# design.net
KiCad netlist of a schematic drawn in Altium Designer
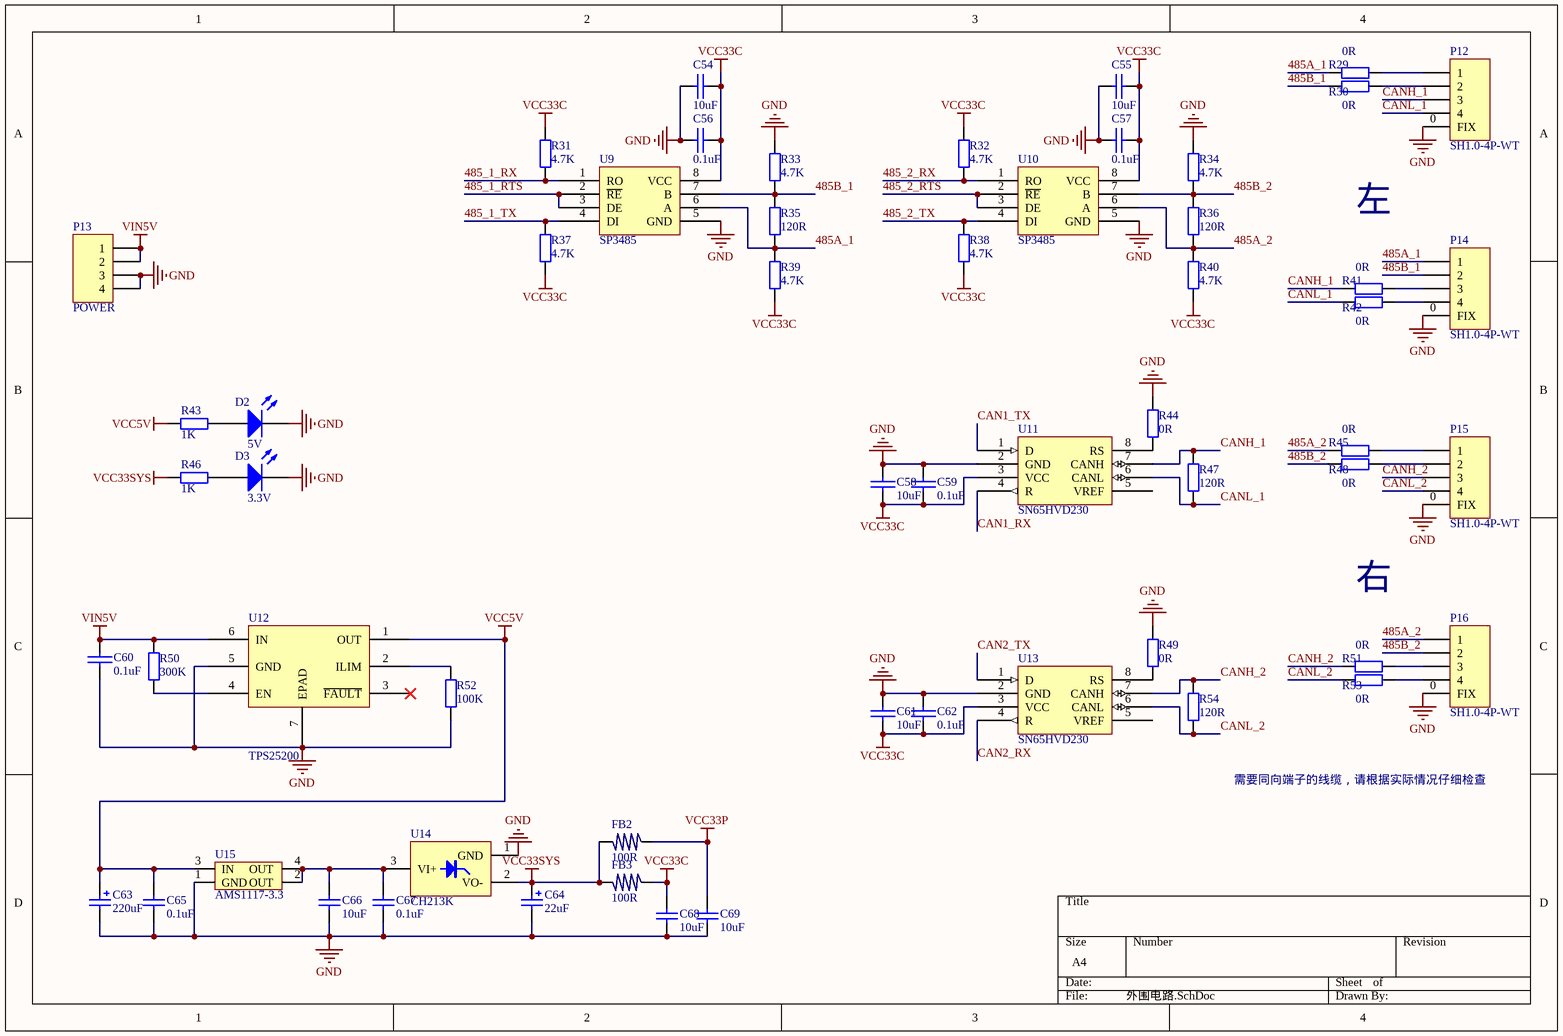
[diagram p0: 外围电路.SchDoc]

(export (version "E")
  (design (tool "Eeschema 10.0.6"))
  (components
    (comp (ref "C54")
      (value "10uF")
      (footprint "C0805_M")
      (description "Capacitor")
      (libsource (lib "*") (part "CAP"))
    )
    (comp (ref "C55")
      (value "10uF")
      (footprint "C0805_M")
      (description "Capacitor")
      (libsource (lib "*") (part "CAP"))
    )
    (comp (ref "C56")
      (value "0.1uF")
      (footprint "C0805_M")
      (description "Capacitor")
      (libsource (lib "*") (part "CAP"))
    )
    (comp (ref "C57")
      (value "0.1uF")
      (footprint "C0805_M")
      (description "Capacitor")
      (libsource (lib "*") (part "CAP"))
    )
    (comp (ref "C58")
      (value "10uF")
      (footprint "C0805_M")
      (description "Capacitor")
      (libsource (lib "*") (part "CAP"))
    )
    (comp (ref "C59")
      (value "0.1uF")
      (footprint "C0805_M")
      (description "Capacitor")
      (libsource (lib "*") (part "CAP"))
    )
    (comp (ref "C60")
      (value "0.1uF")
      (footprint "C0805_M")
      (description "Capacitor")
      (libsource (lib "*") (part "CAP"))
    )
    (comp (ref "C61")
      (value "10uF")
      (footprint "C0805_M")
      (description "Capacitor")
      (libsource (lib "*") (part "CAP"))
    )
    (comp (ref "C62")
      (value "0.1uF")
      (footprint "C0805_M")
      (description "Capacitor")
      (libsource (lib "*") (part "CAP"))
    )
    (comp (ref "C63")
      (value "220uF")
      (footprint "CS 6*6 - R")
      (description "Polarized Capacitor (Axial)")
      (fields (field (name "PUBLISHER") "Altium Limited"))
      (libsource (lib "Miscellaneous Devices") (part "Cap Pol2"))
    )
    (comp (ref "C64")
      (value "22uF")
      (footprint "CS 6*6 - R")
      (description "Polarized Capacitor (Axial)")
      (fields (field (name "PUBLISHER") "Altium Limited"))
      (libsource (lib "Miscellaneous Devices") (part "Cap Pol2"))
    )
    (comp (ref "C65")
      (value "0.1uF")
      (footprint "C0805_M")
      (description "Capacitor")
      (fields (field (name "PUBLISHER") "Altium Limited"))
      (libsource (lib "Miscellaneous Devices") (part "Cap"))
    )
    (comp (ref "C66")
      (value "10uF")
      (footprint "C0805_M")
      (description "Capacitor")
      (fields (field (name "PUBLISHER") "Altium Limited"))
      (libsource (lib "Miscellaneous Devices") (part "Cap"))
    )
    (comp (ref "C67")
      (value "0.1uF")
      (footprint "C0805_M")
      (description "Capacitor")
      (fields (field (name "PUBLISHER") "Altium Limited"))
      (libsource (lib "Miscellaneous Devices") (part "Cap"))
    )
    (comp (ref "C68")
      (value "10uF")
      (footprint "C0805_M")
      (description "Capacitor")
      (fields (field (name "PUBLISHER") "Altium Limited"))
      (libsource (lib "Miscellaneous Devices") (part "Cap"))
    )
    (comp (ref "C69")
      (value "10uF")
      (footprint "C0805_M")
      (description "Capacitor")
      (fields (field (name "PUBLISHER") "Altium Limited"))
      (libsource (lib "Miscellaneous Devices") (part "Cap"))
    )
    (comp (ref "D2")
      (value "5V")
      (footprint "LED0805_G")
      (description "Typical RED GaAs LED")
      (fields (field (name "PUBLISHER") "Altium Limited"))
      (libsource (lib "Miscellaneous Devices") (part "LED1"))
    )
    (comp (ref "D3")
      (value "3.3V")
      (footprint "LED0805_G")
      (description "Typical RED GaAs LED")
      (fields (field (name "PUBLISHER") "Altium Limited"))
      (libsource (lib "Miscellaneous Devices") (part "LED1"))
    )
    (comp (ref "FB2") (value "100R") (footprint "R0805_M") (libsource (lib "EXPLORER") (part "L")))
    (comp (ref "FB3") (value "100R") (footprint "R0805_M") (libsource (lib "EXPLORER") (part "L")))
    (comp (ref "P12")
      (value "SH1.0-4P-WT")
      (footprint "SH1.0-LT-4P")
      (description "Header, 5-Pin")
      (fields (field (name "PUBLISHER") "Altium Limited"))
      (libsource (lib "Miscellaneous Connectors") (part "Header 5"))
    )
    (comp (ref "P13")
      (value "POWER")
      (footprint "XH2.54-LI-4P")
      (description "Header, 4-Pin")
      (fields (field (name "PUBLISHER") "Altium Limited"))
      (libsource (lib "Miscellaneous Connectors") (part "Header 4"))
    )
    (comp (ref "P14")
      (value "SH1.0-4P-WT")
      (footprint "SH1.0-LT-4P")
      (description "Header, 5-Pin")
      (fields (field (name "PUBLISHER") "Altium Limited"))
      (libsource (lib "Miscellaneous Connectors") (part "Header 5"))
    )
    (comp (ref "P15")
      (value "SH1.0-4P-WT")
      (footprint "SH1.0-LT-4P")
      (description "Header, 5-Pin")
      (fields (field (name "PUBLISHER") "Altium Limited"))
      (libsource (lib "Miscellaneous Connectors") (part "Header 5"))
    )
    (comp (ref "P16")
      (value "SH1.0-4P-WT")
      (footprint "SH1.0-LT-4P")
      (description "Header, 5-Pin")
      (fields (field (name "PUBLISHER") "Altium Limited"))
      (libsource (lib "Miscellaneous Connectors") (part "Header 5"))
    )
    (comp (ref "R29")
      (value "0R")
      (footprint "R0805_M")
      (description "Resistor")
      (fields (field (name "PUBLISHER") "Altium Limited"))
      (libsource (lib "Miscellaneous Devices") (part "Res2"))
    )
    (comp (ref "R30")
      (value "0R")
      (footprint "R0805_M")
      (description "Resistor")
      (fields (field (name "PUBLISHER") "Altium Limited"))
      (libsource (lib "Miscellaneous Devices") (part "Res2"))
    )
    (comp (ref "R31")
      (value "4.7K")
      (footprint "R0805_M")
      (description "Resistor")
      (fields (field (name "PUBLISHER") "Altium Limited"))
      (libsource (lib "") (part "Res2_1"))
    )
    (comp (ref "R32")
      (value "4.7K")
      (footprint "R0805_M")
      (description "Resistor")
      (fields (field (name "PUBLISHER") "Altium Limited"))
      (libsource (lib "") (part "Res2_1"))
    )
    (comp (ref "R33")
      (value "4.7K")
      (footprint "R0805_M")
      (description "Resistor")
      (fields (field (name "PUBLISHER") "Altium Limited"))
      (libsource (lib "") (part "Res2_1"))
    )
    (comp (ref "R34")
      (value "4.7K")
      (footprint "R0805_M")
      (description "Resistor")
      (fields (field (name "PUBLISHER") "Altium Limited"))
      (libsource (lib "") (part "Res2_1"))
    )
    (comp (ref "R35")
      (value "120R")
      (footprint "R0805_M")
      (description "Resistor")
      (fields (field (name "PUBLISHER") "Altium Limited"))
      (libsource (lib "") (part "Res2_1"))
    )
    (comp (ref "R36")
      (value "120R")
      (footprint "R0805_M")
      (description "Resistor")
      (fields (field (name "PUBLISHER") "Altium Limited"))
      (libsource (lib "") (part "Res2_1"))
    )
    (comp (ref "R37")
      (value "4.7K")
      (footprint "R0805_M")
      (description "Resistor")
      (fields (field (name "PUBLISHER") "Altium Limited"))
      (libsource (lib "") (part "Res2_1"))
    )
    (comp (ref "R38")
      (value "4.7K")
      (footprint "R0805_M")
      (description "Resistor")
      (fields (field (name "PUBLISHER") "Altium Limited"))
      (libsource (lib "") (part "Res2_1"))
    )
    (comp (ref "R39")
      (value "4.7K")
      (footprint "R0805_M")
      (description "Resistor")
      (fields (field (name "PUBLISHER") "Altium Limited"))
      (libsource (lib "") (part "Res2_1"))
    )
    (comp (ref "R40")
      (value "4.7K")
      (footprint "R0805_M")
      (description "Resistor")
      (fields (field (name "PUBLISHER") "Altium Limited"))
      (libsource (lib "") (part "Res2_1"))
    )
    (comp (ref "R41")
      (value "0R")
      (footprint "R0805_M")
      (description "Resistor")
      (fields (field (name "PUBLISHER") "Altium Limited"))
      (libsource (lib "Miscellaneous Devices") (part "Res2"))
    )
    (comp (ref "R42")
      (value "0R")
      (footprint "R0805_M")
      (description "Resistor")
      (fields (field (name "PUBLISHER") "Altium Limited"))
      (libsource (lib "Miscellaneous Devices") (part "Res2"))
    )
    (comp (ref "R43")
      (value "1K")
      (footprint "R0805_M")
      (description "Resistor")
      (fields (field (name "PUBLISHER") "Altium Limited"))
      (libsource (lib "Miscellaneous Devices") (part "Res2"))
    )
    (comp (ref "R44")
      (value "0R")
      (footprint "R0805_M")
      (description "Resistor")
      (fields (field (name "PUBLISHER") "Altium Limited"))
      (libsource (lib "") (part "Res2_1"))
    )
    (comp (ref "R45")
      (value "0R")
      (footprint "R0805_M")
      (description "Resistor")
      (fields (field (name "PUBLISHER") "Altium Limited"))
      (libsource (lib "Miscellaneous Devices") (part "Res2"))
    )
    (comp (ref "R46")
      (value "1K")
      (footprint "R0805_M")
      (description "Resistor")
      (fields (field (name "PUBLISHER") "Altium Limited"))
      (libsource (lib "Miscellaneous Devices") (part "Res2"))
    )
    (comp (ref "R47")
      (value "120R")
      (footprint "R0805_M")
      (description "Resistor")
      (fields (field (name "PUBLISHER") "Altium Limited"))
      (libsource (lib "") (part "Res2_1"))
    )
    (comp (ref "R48")
      (value "0R")
      (footprint "R0805_M")
      (description "Resistor")
      (fields (field (name "PUBLISHER") "Altium Limited"))
      (libsource (lib "Miscellaneous Devices") (part "Res2"))
    )
    (comp (ref "R49")
      (value "0R")
      (footprint "R0805_M")
      (description "Resistor")
      (fields (field (name "PUBLISHER") "Altium Limited"))
      (libsource (lib "") (part "Res2_1"))
    )
    (comp (ref "R50")
      (value "300K")
      (footprint "R0805_M")
      (description "Resistor")
      (fields (field (name "PUBLISHER") "Altium Limited"))
      (libsource (lib "") (part "Res2_1"))
    )
    (comp (ref "R51")
      (value "0R")
      (footprint "R0805_M")
      (description "Resistor")
      (fields (field (name "PUBLISHER") "Altium Limited"))
      (libsource (lib "Miscellaneous Devices") (part "Res2"))
    )
    (comp (ref "R52")
      (value "100K")
      (footprint "R0805_M")
      (description "Resistor")
      (fields (field (name "PUBLISHER") "Altium Limited"))
      (libsource (lib "") (part "Res2_1"))
    )
    (comp (ref "R53")
      (value "0R")
      (footprint "R0805_M")
      (description "Resistor")
      (fields (field (name "PUBLISHER") "Altium Limited"))
      (libsource (lib "Miscellaneous Devices") (part "Res2"))
    )
    (comp (ref "R54")
      (value "120R")
      (footprint "R0805_M")
      (description "Resistor")
      (fields (field (name "PUBLISHER") "Altium Limited"))
      (libsource (lib "") (part "Res2_1"))
    )
    (comp (ref "U9") (value "SP3485") (footprint "SOIC-8") (libsource (lib "XL6005") (part "SP3485")))
    (comp (ref "U10") (value "SP3485") (footprint "SOIC-8") (libsource (lib "XL6005") (part "SP3485")))
    (comp (ref "U11")
      (value "SN65HVD230")
      (footprint "SOIC-8")
      (libsource (lib "XL6005") (part "SN65HVD230/1"))
    )
    (comp (ref "U12")
      (value "TPS25200")
      (footprint "WSON-6")
      (libsource (lib "7688A原理图封装") (part "TPS25200"))
    )
    (comp (ref "U13")
      (value "SN65HVD230")
      (footprint "SOIC-8")
      (libsource (lib "XL6005") (part "SN65HVD230/1"))
    )
    (comp (ref "U14")
      (value "CH213K")
      (footprint "SOT-23-3")
      (description "Ideal Diode 5V*1A")
      (libsource (lib "CHXXX") (part "CH213K"))
    )
    (comp (ref "U15")
      (value "AMS1117-3.3")
      (footprint "2.02-SOT封装:SOT223_M")
      (libsource (lib "Explorer STM32F407封装库") (part "AMS1117"))
    )
  )
  (nets
    (net (code "1") (name "/485A_1") (class "Default")
      (node (ref "P14") (pin "1") (pinfunction "1_1") (pintype "passive"))
      (node (ref "R29") (pin "2") (pinfunction "2_2") (pintype "passive"))
      (node (ref "R35") (pin "1") (pinfunction "1_1") (pintype "passive"))
      (node (ref "R39") (pin "2") (pinfunction "2_2") (pintype "passive"))
      (node (ref "U9") (pin "6") (pinfunction "A_6") (pintype "passive"))
    )
    (net (code "2") (name "/485A_2") (class "Default")
      (node (ref "P16") (pin "1") (pinfunction "1_1") (pintype "passive"))
      (node (ref "R36") (pin "1") (pinfunction "1_1") (pintype "passive"))
      (node (ref "R40") (pin "2") (pinfunction "2_2") (pintype "passive"))
      (node (ref "R45") (pin "2") (pinfunction "2_2") (pintype "passive"))
      (node (ref "U10") (pin "6") (pinfunction "A_6") (pintype "passive"))
    )
    (net (code "3") (name "/485B_1") (class "Default")
      (node (ref "P14") (pin "2") (pinfunction "2_2") (pintype "passive"))
      (node (ref "R30") (pin "2") (pinfunction "2_2") (pintype "passive"))
      (node (ref "R33") (pin "1") (pinfunction "1_1") (pintype "passive"))
      (node (ref "R35") (pin "2") (pinfunction "2_2") (pintype "passive"))
      (node (ref "U9") (pin "7") (pinfunction "B_7") (pintype "passive"))
    )
    (net (code "4") (name "/485B_2") (class "Default")
      (node (ref "P16") (pin "2") (pinfunction "2_2") (pintype "passive"))
      (node (ref "R34") (pin "1") (pinfunction "1_1") (pintype "passive"))
      (node (ref "R36") (pin "2") (pinfunction "2_2") (pintype "passive"))
      (node (ref "R48") (pin "2") (pinfunction "2_2") (pintype "passive"))
      (node (ref "U10") (pin "7") (pinfunction "B_7") (pintype "passive"))
    )
    (net (code "5") (name "/485_1_RTS") (class "Default")
      (node (ref "U9") (pin "2") (pinfunction "~{RE}_2") (pintype "passive"))
      (node (ref "U9") (pin "3") (pinfunction "DE_3") (pintype "passive"))
    )
    (net (code "6") (name "/485_1_RX") (class "Default")
      (node (ref "R31") (pin "1") (pinfunction "1_1") (pintype "passive"))
      (node (ref "U9") (pin "1") (pinfunction "RO_1") (pintype "passive"))
    )
    (net (code "7") (name "/485_1_TX") (class "Default")
      (node (ref "R37") (pin "2") (pinfunction "2_2") (pintype "passive"))
      (node (ref "U9") (pin "4") (pinfunction "DI_4") (pintype "passive"))
    )
    (net (code "8") (name "/485_2_RTS") (class "Default")
      (node (ref "U10") (pin "2") (pinfunction "~{RE}_2") (pintype "passive"))
      (node (ref "U10") (pin "3") (pinfunction "DE_3") (pintype "passive"))
    )
    (net (code "9") (name "/485_2_RX") (class "Default")
      (node (ref "R32") (pin "1") (pinfunction "1_1") (pintype "passive"))
      (node (ref "U10") (pin "1") (pinfunction "RO_1") (pintype "passive"))
    )
    (net (code "10") (name "/485_2_TX") (class "Default")
      (node (ref "R38") (pin "2") (pinfunction "2_2") (pintype "passive"))
      (node (ref "U10") (pin "4") (pinfunction "DI_4") (pintype "passive"))
    )
    (net (code "11") (name "/CAN1_RX") (class "Default")
      (node (ref "U11") (pin "4") (pinfunction "R_4") (pintype "output"))
    )
    (net (code "12") (name "/CAN1_TX") (class "Default")
      (node (ref "U11") (pin "1") (pinfunction "D_1") (pintype "input"))
    )
    (net (code "13") (name "/CAN2_RX") (class "Default")
      (node (ref "U13") (pin "4") (pinfunction "R_4") (pintype "output"))
    )
    (net (code "14") (name "/CAN2_TX") (class "Default")
      (node (ref "U13") (pin "1") (pinfunction "D_1") (pintype "input"))
    )
    (net (code "15") (name "/CANH_1") (class "Default")
      (node (ref "P12") (pin "3") (pinfunction "3_3") (pintype "passive"))
      (node (ref "R41") (pin "2") (pinfunction "2_2") (pintype "passive"))
      (node (ref "R47") (pin "2") (pinfunction "2_2") (pintype "passive"))
      (node (ref "U11") (pin "7") (pinfunction "CANH_7") (pintype "bidirectional"))
    )
    (net (code "16") (name "/CANH_2") (class "Default")
      (node (ref "P15") (pin "3") (pinfunction "3_3") (pintype "passive"))
      (node (ref "R51") (pin "2") (pinfunction "2_2") (pintype "passive"))
      (node (ref "R54") (pin "2") (pinfunction "2_2") (pintype "passive"))
      (node (ref "U13") (pin "7") (pinfunction "CANH_7") (pintype "bidirectional"))
    )
    (net (code "17") (name "/CANL_1") (class "Default")
      (node (ref "P12") (pin "4") (pinfunction "4_4") (pintype "passive"))
      (node (ref "R42") (pin "2") (pinfunction "2_2") (pintype "passive"))
      (node (ref "R47") (pin "1") (pinfunction "1_1") (pintype "passive"))
      (node (ref "U11") (pin "6") (pinfunction "CANL_6") (pintype "bidirectional"))
    )
    (net (code "18") (name "/CANL_2") (class "Default")
      (node (ref "P15") (pin "4") (pinfunction "4_4") (pintype "passive"))
      (node (ref "R53") (pin "2") (pinfunction "2_2") (pintype "passive"))
      (node (ref "R54") (pin "1") (pinfunction "1_1") (pintype "passive"))
      (node (ref "U13") (pin "6") (pinfunction "CANL_6") (pintype "bidirectional"))
    )
    (net (code "19") (name "GND") (class "Default")
      (node (ref "C54") (pin "1") (pinfunction "1_1") (pintype "passive"))
      (node (ref "C55") (pin "1") (pinfunction "1_1") (pintype "passive"))
      (node (ref "C56") (pin "1") (pinfunction "1_1") (pintype "passive"))
      (node (ref "C57") (pin "1") (pinfunction "1_1") (pintype "passive"))
      (node (ref "C58") (pin "2") (pinfunction "2_2") (pintype "passive"))
      (node (ref "C59") (pin "2") (pinfunction "2_2") (pintype "passive"))
      (node (ref "C60") (pin "2") (pinfunction "2_2") (pintype "passive"))
      (node (ref "C61") (pin "2") (pinfunction "2_2") (pintype "passive"))
      (node (ref "C62") (pin "2") (pinfunction "2_2") (pintype "passive"))
      (node (ref "C63") (pin "2") (pinfunction "2_2") (pintype "passive"))
      (node (ref "C64") (pin "2") (pinfunction "2_2") (pintype "passive"))
      (node (ref "C65") (pin "1") (pinfunction "1_1") (pintype "passive"))
      (node (ref "C66") (pin "1") (pinfunction "1_1") (pintype "passive"))
      (node (ref "C67") (pin "1") (pinfunction "1_1") (pintype "passive"))
      (node (ref "C68") (pin "1") (pinfunction "1_1") (pintype "passive"))
      (node (ref "C69") (pin "1") (pinfunction "1_1") (pintype "passive"))
      (node (ref "D2") (pin "2") (pinfunction "K_2") (pintype "passive"))
      (node (ref "D3") (pin "2") (pinfunction "K_2") (pintype "passive"))
      (node (ref "P12") (pin "0") (pinfunction "FIX_0") (pintype "passive"))
      (node (ref "P13") (pin "3") (pinfunction "3_3") (pintype "passive"))
      (node (ref "P13") (pin "4") (pinfunction "4_4") (pintype "passive"))
      (node (ref "P14") (pin "0") (pinfunction "FIX_0") (pintype "passive"))
      (node (ref "P15") (pin "0") (pinfunction "FIX_0") (pintype "passive"))
      (node (ref "P16") (pin "0") (pinfunction "FIX_0") (pintype "passive"))
      (node (ref "R33") (pin "2") (pinfunction "2_2") (pintype "passive"))
      (node (ref "R34") (pin "2") (pinfunction "2_2") (pintype "passive"))
      (node (ref "R44") (pin "2") (pinfunction "2_2") (pintype "passive"))
      (node (ref "R49") (pin "2") (pinfunction "2_2") (pintype "passive"))
      (node (ref "R52") (pin "1") (pinfunction "1_1") (pintype "passive"))
      (node (ref "U10") (pin "5") (pinfunction "GND_5") (pintype "passive"))
      (node (ref "U11") (pin "2") (pinfunction "GND_2") (pintype "passive"))
      (node (ref "U12") (pin "5") (pinfunction "GND_5") (pintype "passive"))
      (node (ref "U12") (pin "7") (pinfunction "EPAD_7") (pintype "passive"))
      (node (ref "U13") (pin "2") (pinfunction "GND_2") (pintype "passive"))
      (node (ref "U14") (pin "1") (pinfunction "GND_1") (pintype "power_in"))
      (node (ref "U15") (pin "1") (pinfunction "GND_1") (pintype "passive"))
      (node (ref "U9") (pin "5") (pinfunction "GND_5") (pintype "passive"))
    )
    (net (code "20") (name "Net-(D2-A)") (class "Default")
      (node (ref "D2") (pin "1") (pinfunction "A_1") (pintype "passive"))
      (node (ref "R43") (pin "1") (pinfunction "1_1") (pintype "passive"))
    )
    (net (code "21") (name "Net-(D3-A)") (class "Default")
      (node (ref "D3") (pin "1") (pinfunction "A_1") (pintype "passive"))
      (node (ref "R46") (pin "1") (pinfunction "1_1") (pintype "passive"))
    )
    (net (code "22") (name "Net-(P12-Pad1)") (class "Default")
      (node (ref "P12") (pin "1") (pinfunction "1_1") (pintype "passive"))
      (node (ref "R29") (pin "1") (pinfunction "1_1") (pintype "passive"))
    )
    (net (code "23") (name "Net-(P12-Pad2)") (class "Default")
      (node (ref "P12") (pin "2") (pinfunction "2_2") (pintype "passive"))
      (node (ref "R30") (pin "1") (pinfunction "1_1") (pintype "passive"))
    )
    (net (code "24") (name "Net-(P14-Pad3)") (class "Default")
      (node (ref "P14") (pin "3") (pinfunction "3_3") (pintype "passive"))
      (node (ref "R41") (pin "1") (pinfunction "1_1") (pintype "passive"))
    )
    (net (code "25") (name "Net-(P14-Pad4)") (class "Default")
      (node (ref "P14") (pin "4") (pinfunction "4_4") (pintype "passive"))
      (node (ref "R42") (pin "1") (pinfunction "1_1") (pintype "passive"))
    )
    (net (code "26") (name "Net-(P15-Pad1)") (class "Default")
      (node (ref "P15") (pin "1") (pinfunction "1_1") (pintype "passive"))
      (node (ref "R45") (pin "1") (pinfunction "1_1") (pintype "passive"))
    )
    (net (code "27") (name "Net-(P15-Pad2)") (class "Default")
      (node (ref "P15") (pin "2") (pinfunction "2_2") (pintype "passive"))
      (node (ref "R48") (pin "1") (pinfunction "1_1") (pintype "passive"))
    )
    (net (code "28") (name "Net-(P16-Pad3)") (class "Default")
      (node (ref "P16") (pin "3") (pinfunction "3_3") (pintype "passive"))
      (node (ref "R51") (pin "1") (pinfunction "1_1") (pintype "passive"))
    )
    (net (code "29") (name "Net-(P16-Pad4)") (class "Default")
      (node (ref "P16") (pin "4") (pinfunction "4_4") (pintype "passive"))
      (node (ref "R53") (pin "1") (pinfunction "1_1") (pintype "passive"))
    )
    (net (code "30") (name "Net-(U11-RS)") (class "Default")
      (node (ref "R44") (pin "1") (pinfunction "1_1") (pintype "passive"))
      (node (ref "U11") (pin "8") (pinfunction "RS_8") (pintype "passive"))
    )
    (net (code "31") (name "Net-(U12-EN)") (class "Default")
      (node (ref "R50") (pin "1") (pinfunction "1_1") (pintype "passive"))
      (node (ref "U12") (pin "4") (pinfunction "EN_4") (pintype "passive"))
    )
    (net (code "32") (name "Net-(U12-ILIM)") (class "Default")
      (node (ref "R52") (pin "2") (pinfunction "2_2") (pintype "passive"))
      (node (ref "U12") (pin "2") (pinfunction "ILIM_2") (pintype "passive"))
    )
    (net (code "33") (name "Net-(U13-RS)") (class "Default")
      (node (ref "R49") (pin "1") (pinfunction "1_1") (pintype "passive"))
      (node (ref "U13") (pin "8") (pinfunction "RS_8") (pintype "passive"))
    )
    (net (code "34") (name "Net-(U14-VI+)") (class "Default")
      (node (ref "C66") (pin "2") (pinfunction "2_2") (pintype "passive"))
      (node (ref "C67") (pin "2") (pinfunction "2_2") (pintype "passive"))
      (node (ref "U14") (pin "3") (pinfunction "VI+_3") (pintype "power_in"))
      (node (ref "U15") (pin "2") (pinfunction "OUT_2") (pintype "passive"))
      (node (ref "U15") (pin "4") (pinfunction "OUT_4") (pintype "passive"))
    )
    (net (code "35") (name "VCC5V") (class "Default")
      (node (ref "C63") (pin "1") (pinfunction "1_1") (pintype "passive"))
      (node (ref "C65") (pin "2") (pinfunction "2_2") (pintype "passive"))
      (node (ref "R43") (pin "2") (pinfunction "2_2") (pintype "passive"))
      (node (ref "U12") (pin "1") (pinfunction "OUT_1") (pintype "passive"))
      (node (ref "U15") (pin "3") (pinfunction "IN_3") (pintype "passive"))
    )
    (net (code "36") (name "VCC33C") (class "Default")
      (node (ref "C54") (pin "2") (pinfunction "2_2") (pintype "passive"))
      (node (ref "C55") (pin "2") (pinfunction "2_2") (pintype "passive"))
      (node (ref "C56") (pin "2") (pinfunction "2_2") (pintype "passive"))
      (node (ref "C57") (pin "2") (pinfunction "2_2") (pintype "passive"))
      (node (ref "C58") (pin "1") (pinfunction "1_1") (pintype "passive"))
      (node (ref "C59") (pin "1") (pinfunction "1_1") (pintype "passive"))
      (node (ref "C61") (pin "1") (pinfunction "1_1") (pintype "passive"))
      (node (ref "C62") (pin "1") (pinfunction "1_1") (pintype "passive"))
      (node (ref "C68") (pin "2") (pinfunction "2_2") (pintype "passive"))
      (node (ref "FB3") (pin "1") (pintype "passive"))
      (node (ref "R31") (pin "2") (pinfunction "2_2") (pintype "passive"))
      (node (ref "R32") (pin "2") (pinfunction "2_2") (pintype "passive"))
      (node (ref "R37") (pin "1") (pinfunction "1_1") (pintype "passive"))
      (node (ref "R38") (pin "1") (pinfunction "1_1") (pintype "passive"))
      (node (ref "R39") (pin "1") (pinfunction "1_1") (pintype "passive"))
      (node (ref "R40") (pin "1") (pinfunction "1_1") (pintype "passive"))
      (node (ref "U10") (pin "8") (pinfunction "VCC_8") (pintype "passive"))
      (node (ref "U11") (pin "3") (pinfunction "VCC_3") (pintype "passive"))
      (node (ref "U13") (pin "3") (pinfunction "VCC_3") (pintype "passive"))
      (node (ref "U9") (pin "8") (pinfunction "VCC_8") (pintype "passive"))
    )
    (net (code "37") (name "VCC33P") (class "Default")
      (node (ref "C69") (pin "2") (pinfunction "2_2") (pintype "passive"))
      (node (ref "FB2") (pin "1") (pintype "passive"))
    )
    (net (code "38") (name "VCC33SYS") (class "Default")
      (node (ref "C64") (pin "1") (pinfunction "1_1") (pintype "passive"))
      (node (ref "FB2") (pin "2") (pintype "passive"))
      (node (ref "FB3") (pin "2") (pintype "passive"))
      (node (ref "R46") (pin "2") (pinfunction "2_2") (pintype "passive"))
      (node (ref "U14") (pin "2") (pinfunction "VO-_2") (pintype "power_in"))
    )
    (net (code "39") (name "VIN5V") (class "Default")
      (node (ref "C60") (pin "1") (pinfunction "1_1") (pintype "passive"))
      (node (ref "P13") (pin "1") (pinfunction "1_1") (pintype "passive"))
      (node (ref "P13") (pin "2") (pinfunction "2_2") (pintype "passive"))
      (node (ref "R50") (pin "2") (pinfunction "2_2") (pintype "passive"))
      (node (ref "U12") (pin "6") (pinfunction "IN_6") (pintype "passive"))
    )
    (net (code "40") (name "unconnected-(U11-VREF-Pad5)") (class "Default")
      (node (ref "U11") (pin "5") (pinfunction "VREF_5") (pintype "passive"))
    )
    (net (code "41") (name "unconnected-(U12-~{FAULT}-Pad3)") (class "Default")
      (node (ref "U12") (pin "3") (pinfunction "~{FAULT}_3") (pintype "passive+no_connect"))
    )
    (net (code "42") (name "unconnected-(U13-VREF-Pad5)") (class "Default")
      (node (ref "U13") (pin "5") (pinfunction "VREF_5") (pintype "passive"))
    )
  )
)
